# 08_LLC_Temperature.net
KiCad netlist of a schematic drawn in Altium Designer
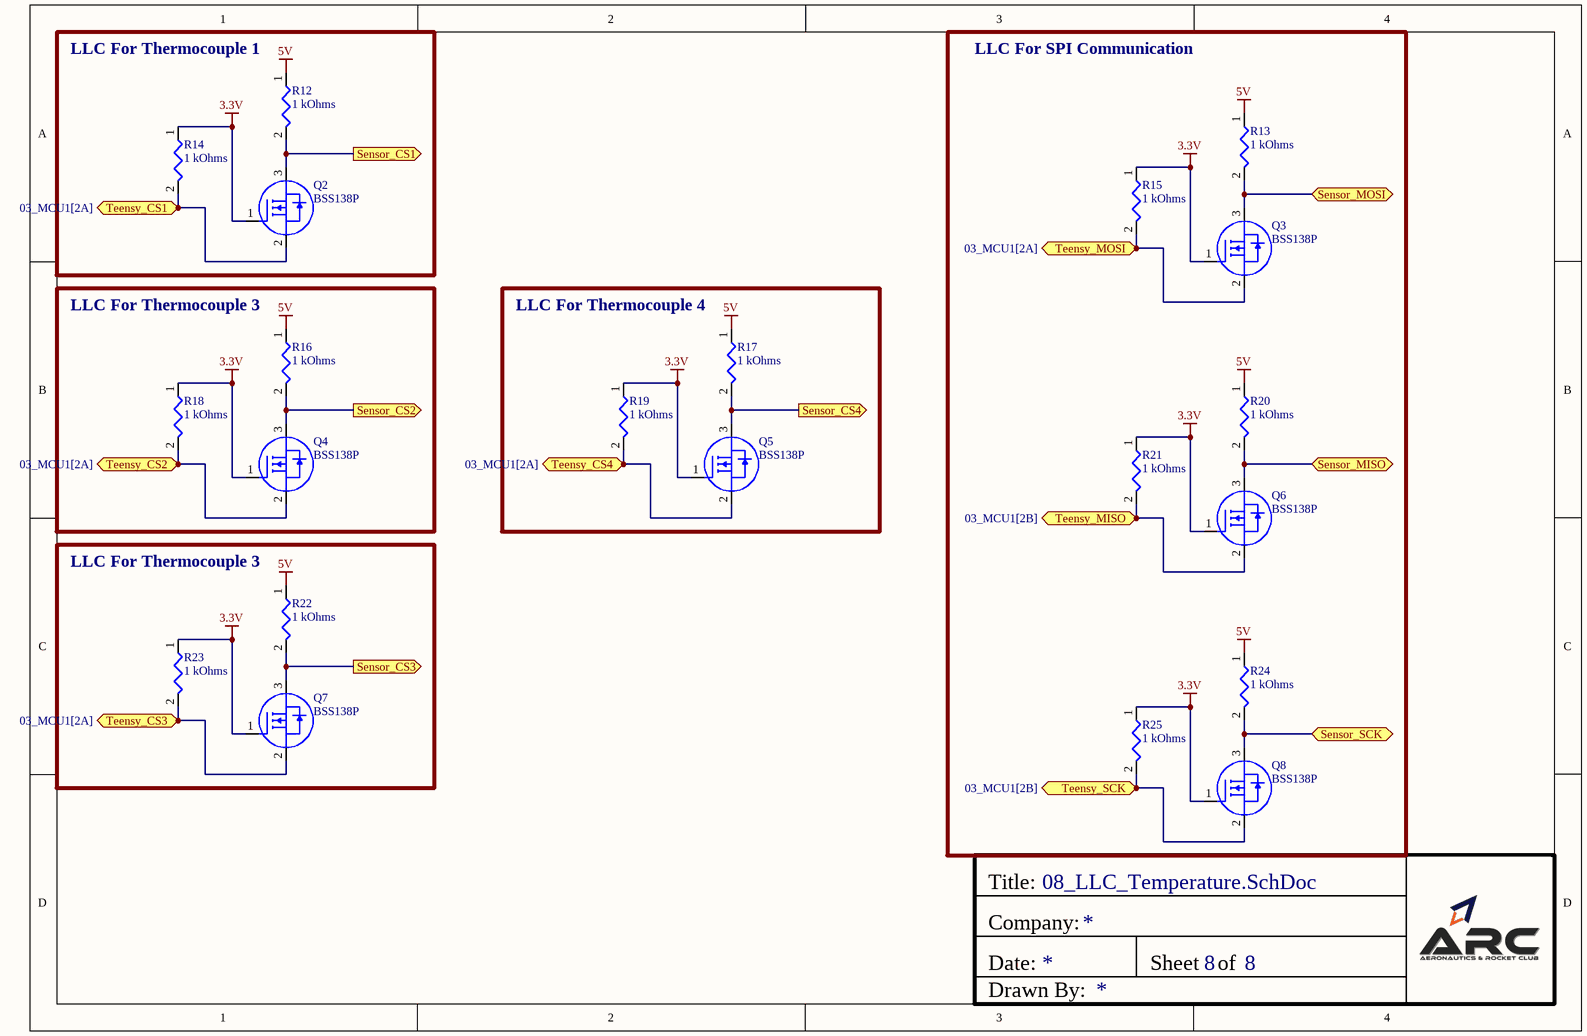
[diagram p0: 08_LLC_Temperature.SchDoc]

(export (version "E")
  (design (tool "Eeschema 10.0.6"))
  (components
    (comp (ref "Q2")
      (value "BSS138P")
      (footprint "BSS138P")
      (description "N-Channel MOSFET BSS138P Series 60 V 1.6 Ohm 350 mW 0.72 nC SMT TrenchMOS FET - SOT-23")
      (fields
        (field (name "MANUFACTURER") "Nexperia")
        (field (name "MANUFACTURER PART NUMBER") "BSS138P,215")
      )
      (libsource (lib "Ground Support_Schlib") (part "BSS138P"))
    )
    (comp (ref "Q3")
      (value "BSS138P")
      (footprint "BSS138P")
      (description "N-Channel MOSFET BSS138P Series 60 V 1.6 Ohm 350 mW 0.72 nC SMT TrenchMOS FET - SOT-23")
      (fields
        (field (name "MANUFACTURER") "Nexperia")
        (field (name "MANUFACTURER PART NUMBER") "BSS138P,215")
      )
      (libsource (lib "Ground Support_Schlib") (part "BSS138P"))
    )
    (comp (ref "Q4")
      (value "BSS138P")
      (footprint "BSS138P")
      (description "N-Channel MOSFET BSS138P Series 60 V 1.6 Ohm 350 mW 0.72 nC SMT TrenchMOS FET - SOT-23")
      (fields
        (field (name "MANUFACTURER") "Nexperia")
        (field (name "MANUFACTURER PART NUMBER") "BSS138P,215")
      )
      (libsource (lib "Ground Support_Schlib") (part "BSS138P"))
    )
    (comp (ref "Q5")
      (value "BSS138P")
      (footprint "BSS138P")
      (description "N-Channel MOSFET BSS138P Series 60 V 1.6 Ohm 350 mW 0.72 nC SMT TrenchMOS FET - SOT-23")
      (fields
        (field (name "MANUFACTURER") "Nexperia")
        (field (name "MANUFACTURER PART NUMBER") "BSS138P,215")
      )
      (libsource (lib "Ground Support_Schlib") (part "BSS138P"))
    )
    (comp (ref "Q6")
      (value "BSS138P")
      (footprint "BSS138P")
      (description "N-Channel MOSFET BSS138P Series 60 V 1.6 Ohm 350 mW 0.72 nC SMT TrenchMOS FET - SOT-23")
      (fields
        (field (name "MANUFACTURER") "Nexperia")
        (field (name "MANUFACTURER PART NUMBER") "BSS138P,215")
      )
      (libsource (lib "Ground Support_Schlib") (part "BSS138P"))
    )
    (comp (ref "Q7")
      (value "BSS138P")
      (footprint "BSS138P")
      (description "N-Channel MOSFET BSS138P Series 60 V 1.6 Ohm 350 mW 0.72 nC SMT TrenchMOS FET - SOT-23")
      (fields
        (field (name "MANUFACTURER") "Nexperia")
        (field (name "MANUFACTURER PART NUMBER") "BSS138P,215")
      )
      (libsource (lib "Ground Support_Schlib") (part "BSS138P"))
    )
    (comp (ref "Q8")
      (value "BSS138P")
      (footprint "BSS138P")
      (description "N-Channel MOSFET BSS138P Series 60 V 1.6 Ohm 350 mW 0.72 nC SMT TrenchMOS FET - SOT-23")
      (fields
        (field (name "MANUFACTURER") "Nexperia")
        (field (name "MANUFACTURER PART NUMBER") "BSS138P,215")
      )
      (libsource (lib "Ground Support_Schlib") (part "BSS138P"))
    )
    (comp (ref "R12")
      (value "1 kOhms")
      (footprint "RESC2012X06N")
      (description "1 kOhms ±1% 0.25W, 1/4W Chip Resistor 0805 (2012 Metric) Moisture Resistant Thick Film")
      (fields
        (field (name "MANUFACTURER") "Yageo")
        (field (name "MANUFACTURER PART NUMBER") "RC0805FR-7W1KL")
      )
      (libsource (lib "Ground Support_Schlib") (part "RC0805FR-7W1KL Yageo"))
    )
    (comp (ref "R13")
      (value "1 kOhms")
      (footprint "RESC2012X06N")
      (description "1 kOhms ±1% 0.25W, 1/4W Chip Resistor 0805 (2012 Metric) Moisture Resistant Thick Film")
      (fields
        (field (name "MANUFACTURER") "Yageo")
        (field (name "MANUFACTURER PART NUMBER") "RC0805FR-7W1KL")
      )
      (libsource (lib "Ground Support_Schlib") (part "RC0805FR-7W1KL Yageo"))
    )
    (comp (ref "R14")
      (value "1 kOhms")
      (footprint "RESC2012X06N")
      (description "1 kOhms ±1% 0.25W, 1/4W Chip Resistor 0805 (2012 Metric) Moisture Resistant Thick Film")
      (fields
        (field (name "MANUFACTURER") "Yageo")
        (field (name "MANUFACTURER PART NUMBER") "RC0805FR-7W1KL")
      )
      (libsource (lib "Ground Support_Schlib") (part "RC0805FR-7W1KL Yageo"))
    )
    (comp (ref "R15")
      (value "1 kOhms")
      (footprint "RESC2012X06N")
      (description "1 kOhms ±1% 0.25W, 1/4W Chip Resistor 0805 (2012 Metric) Moisture Resistant Thick Film")
      (fields
        (field (name "MANUFACTURER") "Yageo")
        (field (name "MANUFACTURER PART NUMBER") "RC0805FR-7W1KL")
      )
      (libsource (lib "Ground Support_Schlib") (part "RC0805FR-7W1KL Yageo"))
    )
    (comp (ref "R16")
      (value "1 kOhms")
      (footprint "RESC2012X06N")
      (description "1 kOhms ±1% 0.25W, 1/4W Chip Resistor 0805 (2012 Metric) Moisture Resistant Thick Film")
      (fields
        (field (name "MANUFACTURER") "Yageo")
        (field (name "MANUFACTURER PART NUMBER") "RC0805FR-7W1KL")
      )
      (libsource (lib "Ground Support_Schlib") (part "RC0805FR-7W1KL Yageo"))
    )
    (comp (ref "R17")
      (value "1 kOhms")
      (footprint "RESC2012X06N")
      (description "1 kOhms ±1% 0.25W, 1/4W Chip Resistor 0805 (2012 Metric) Moisture Resistant Thick Film")
      (fields
        (field (name "MANUFACTURER") "Yageo")
        (field (name "MANUFACTURER PART NUMBER") "RC0805FR-7W1KL")
      )
      (libsource (lib "Ground Support_Schlib") (part "RC0805FR-7W1KL Yageo"))
    )
    (comp (ref "R18")
      (value "1 kOhms")
      (footprint "RESC2012X06N")
      (description "1 kOhms ±1% 0.25W, 1/4W Chip Resistor 0805 (2012 Metric) Moisture Resistant Thick Film")
      (fields
        (field (name "MANUFACTURER") "Yageo")
        (field (name "MANUFACTURER PART NUMBER") "RC0805FR-7W1KL")
      )
      (libsource (lib "Ground Support_Schlib") (part "RC0805FR-7W1KL Yageo"))
    )
    (comp (ref "R19")
      (value "1 kOhms")
      (footprint "RESC2012X06N")
      (description "1 kOhms ±1% 0.25W, 1/4W Chip Resistor 0805 (2012 Metric) Moisture Resistant Thick Film")
      (fields
        (field (name "MANUFACTURER") "Yageo")
        (field (name "MANUFACTURER PART NUMBER") "RC0805FR-7W1KL")
      )
      (libsource (lib "Ground Support_Schlib") (part "RC0805FR-7W1KL Yageo"))
    )
    (comp (ref "R20")
      (value "1 kOhms")
      (footprint "RESC2012X06N")
      (description "1 kOhms ±1% 0.25W, 1/4W Chip Resistor 0805 (2012 Metric) Moisture Resistant Thick Film")
      (fields
        (field (name "MANUFACTURER") "Yageo")
        (field (name "MANUFACTURER PART NUMBER") "RC0805FR-7W1KL")
      )
      (libsource (lib "Ground Support_Schlib") (part "RC0805FR-7W1KL Yageo"))
    )
    (comp (ref "R21")
      (value "1 kOhms")
      (footprint "RESC2012X06N")
      (description "1 kOhms ±1% 0.25W, 1/4W Chip Resistor 0805 (2012 Metric) Moisture Resistant Thick Film")
      (fields
        (field (name "MANUFACTURER") "Yageo")
        (field (name "MANUFACTURER PART NUMBER") "RC0805FR-7W1KL")
      )
      (libsource (lib "Ground Support_Schlib") (part "RC0805FR-7W1KL Yageo"))
    )
    (comp (ref "R22")
      (value "1 kOhms")
      (footprint "RESC2012X06N")
      (description "1 kOhms ±1% 0.25W, 1/4W Chip Resistor 0805 (2012 Metric) Moisture Resistant Thick Film")
      (fields
        (field (name "MANUFACTURER") "Yageo")
        (field (name "MANUFACTURER PART NUMBER") "RC0805FR-7W1KL")
      )
      (libsource (lib "Ground Support_Schlib") (part "RC0805FR-7W1KL Yageo"))
    )
    (comp (ref "R23")
      (value "1 kOhms")
      (footprint "RESC2012X06N")
      (description "1 kOhms ±1% 0.25W, 1/4W Chip Resistor 0805 (2012 Metric) Moisture Resistant Thick Film")
      (fields
        (field (name "MANUFACTURER") "Yageo")
        (field (name "MANUFACTURER PART NUMBER") "RC0805FR-7W1KL")
      )
      (libsource (lib "Ground Support_Schlib") (part "RC0805FR-7W1KL Yageo"))
    )
    (comp (ref "R24")
      (value "1 kOhms")
      (footprint "RESC2012X06N")
      (description "1 kOhms ±1% 0.25W, 1/4W Chip Resistor 0805 (2012 Metric) Moisture Resistant Thick Film")
      (fields
        (field (name "MANUFACTURER") "Yageo")
        (field (name "MANUFACTURER PART NUMBER") "RC0805FR-7W1KL")
      )
      (libsource (lib "Ground Support_Schlib") (part "RC0805FR-7W1KL Yageo"))
    )
    (comp (ref "R25")
      (value "1 kOhms")
      (footprint "RESC2012X06N")
      (description "1 kOhms ±1% 0.25W, 1/4W Chip Resistor 0805 (2012 Metric) Moisture Resistant Thick Film")
      (fields
        (field (name "MANUFACTURER") "Yageo")
        (field (name "MANUFACTURER PART NUMBER") "RC0805FR-7W1KL")
      )
      (libsource (lib "Ground Support_Schlib") (part "RC0805FR-7W1KL Yageo"))
    )
  )
  (nets
    (net (code "1") (name "/Sensor_CS1") (class "Default")
      (node (ref "Q2") (pin "3") (pinfunction "D_3") (pintype "passive"))
      (node (ref "R12") (pin "2") (pinfunction "2_2") (pintype "passive"))
    )
    (net (code "2") (name "/Sensor_CS2") (class "Default")
      (node (ref "Q4") (pin "3") (pinfunction "D_3") (pintype "passive"))
      (node (ref "R16") (pin "2") (pinfunction "2_2") (pintype "passive"))
    )
    (net (code "3") (name "/Sensor_CS3") (class "Default")
      (node (ref "Q7") (pin "3") (pinfunction "D_3") (pintype "passive"))
      (node (ref "R22") (pin "2") (pinfunction "2_2") (pintype "passive"))
    )
    (net (code "4") (name "/Sensor_CS4") (class "Default")
      (node (ref "Q5") (pin "3") (pinfunction "D_3") (pintype "passive"))
      (node (ref "R17") (pin "2") (pinfunction "2_2") (pintype "passive"))
    )
    (net (code "5") (name "/Sensor_MISO") (class "Default")
      (node (ref "Q6") (pin "3") (pinfunction "D_3") (pintype "passive"))
      (node (ref "R20") (pin "2") (pinfunction "2_2") (pintype "passive"))
    )
    (net (code "6") (name "/Sensor_MOSI") (class "Default")
      (node (ref "Q3") (pin "3") (pinfunction "D_3") (pintype "passive"))
      (node (ref "R13") (pin "2") (pinfunction "2_2") (pintype "passive"))
    )
    (net (code "7") (name "/Sensor_SCK") (class "Default")
      (node (ref "Q8") (pin "3") (pinfunction "D_3") (pintype "passive"))
      (node (ref "R24") (pin "2") (pinfunction "2_2") (pintype "passive"))
    )
    (net (code "8") (name "/Teensy_CS1") (class "Default")
      (node (ref "Q2") (pin "2") (pinfunction "S_2") (pintype "passive"))
      (node (ref "R14") (pin "2") (pinfunction "2_2") (pintype "passive"))
    )
    (net (code "9") (name "/Teensy_CS2") (class "Default")
      (node (ref "Q4") (pin "2") (pinfunction "S_2") (pintype "passive"))
      (node (ref "R18") (pin "2") (pinfunction "2_2") (pintype "passive"))
    )
    (net (code "10") (name "/Teensy_CS3") (class "Default")
      (node (ref "Q7") (pin "2") (pinfunction "S_2") (pintype "passive"))
      (node (ref "R23") (pin "2") (pinfunction "2_2") (pintype "passive"))
    )
    (net (code "11") (name "/Teensy_CS4") (class "Default")
      (node (ref "Q5") (pin "2") (pinfunction "S_2") (pintype "passive"))
      (node (ref "R19") (pin "2") (pinfunction "2_2") (pintype "passive"))
    )
    (net (code "12") (name "/Teensy_MISO") (class "Default")
      (node (ref "Q6") (pin "2") (pinfunction "S_2") (pintype "passive"))
      (node (ref "R21") (pin "2") (pinfunction "2_2") (pintype "passive"))
    )
    (net (code "13") (name "/Teensy_MOSI") (class "Default")
      (node (ref "Q3") (pin "2") (pinfunction "S_2") (pintype "passive"))
      (node (ref "R15") (pin "2") (pinfunction "2_2") (pintype "passive"))
    )
    (net (code "14") (name "/Teensy_SCK") (class "Default")
      (node (ref "Q8") (pin "2") (pinfunction "S_2") (pintype "passive"))
      (node (ref "R25") (pin "2") (pinfunction "2_2") (pintype "passive"))
    )
    (net (code "15") (name "3.3V") (class "Default")
      (node (ref "Q2") (pin "1") (pinfunction "G_1") (pintype "passive"))
      (node (ref "Q3") (pin "1") (pinfunction "G_1") (pintype "passive"))
      (node (ref "Q4") (pin "1") (pinfunction "G_1") (pintype "passive"))
      (node (ref "Q5") (pin "1") (pinfunction "G_1") (pintype "passive"))
      (node (ref "Q6") (pin "1") (pinfunction "G_1") (pintype "passive"))
      (node (ref "Q7") (pin "1") (pinfunction "G_1") (pintype "passive"))
      (node (ref "Q8") (pin "1") (pinfunction "G_1") (pintype "passive"))
      (node (ref "R14") (pin "1") (pinfunction "1_1") (pintype "passive"))
      (node (ref "R15") (pin "1") (pinfunction "1_1") (pintype "passive"))
      (node (ref "R18") (pin "1") (pinfunction "1_1") (pintype "passive"))
      (node (ref "R19") (pin "1") (pinfunction "1_1") (pintype "passive"))
      (node (ref "R21") (pin "1") (pinfunction "1_1") (pintype "passive"))
      (node (ref "R23") (pin "1") (pinfunction "1_1") (pintype "passive"))
      (node (ref "R25") (pin "1") (pinfunction "1_1") (pintype "passive"))
    )
    (net (code "16") (name "5V") (class "Default")
      (node (ref "R12") (pin "1") (pinfunction "1_1") (pintype "passive"))
      (node (ref "R13") (pin "1") (pinfunction "1_1") (pintype "passive"))
      (node (ref "R16") (pin "1") (pinfunction "1_1") (pintype "passive"))
      (node (ref "R17") (pin "1") (pinfunction "1_1") (pintype "passive"))
      (node (ref "R20") (pin "1") (pinfunction "1_1") (pintype "passive"))
      (node (ref "R22") (pin "1") (pinfunction "1_1") (pintype "passive"))
      (node (ref "R24") (pin "1") (pinfunction "1_1") (pintype "passive"))
    )
  )
)
